# ADS1282.net
KiCad netlist of a schematic drawn in Altium Designer
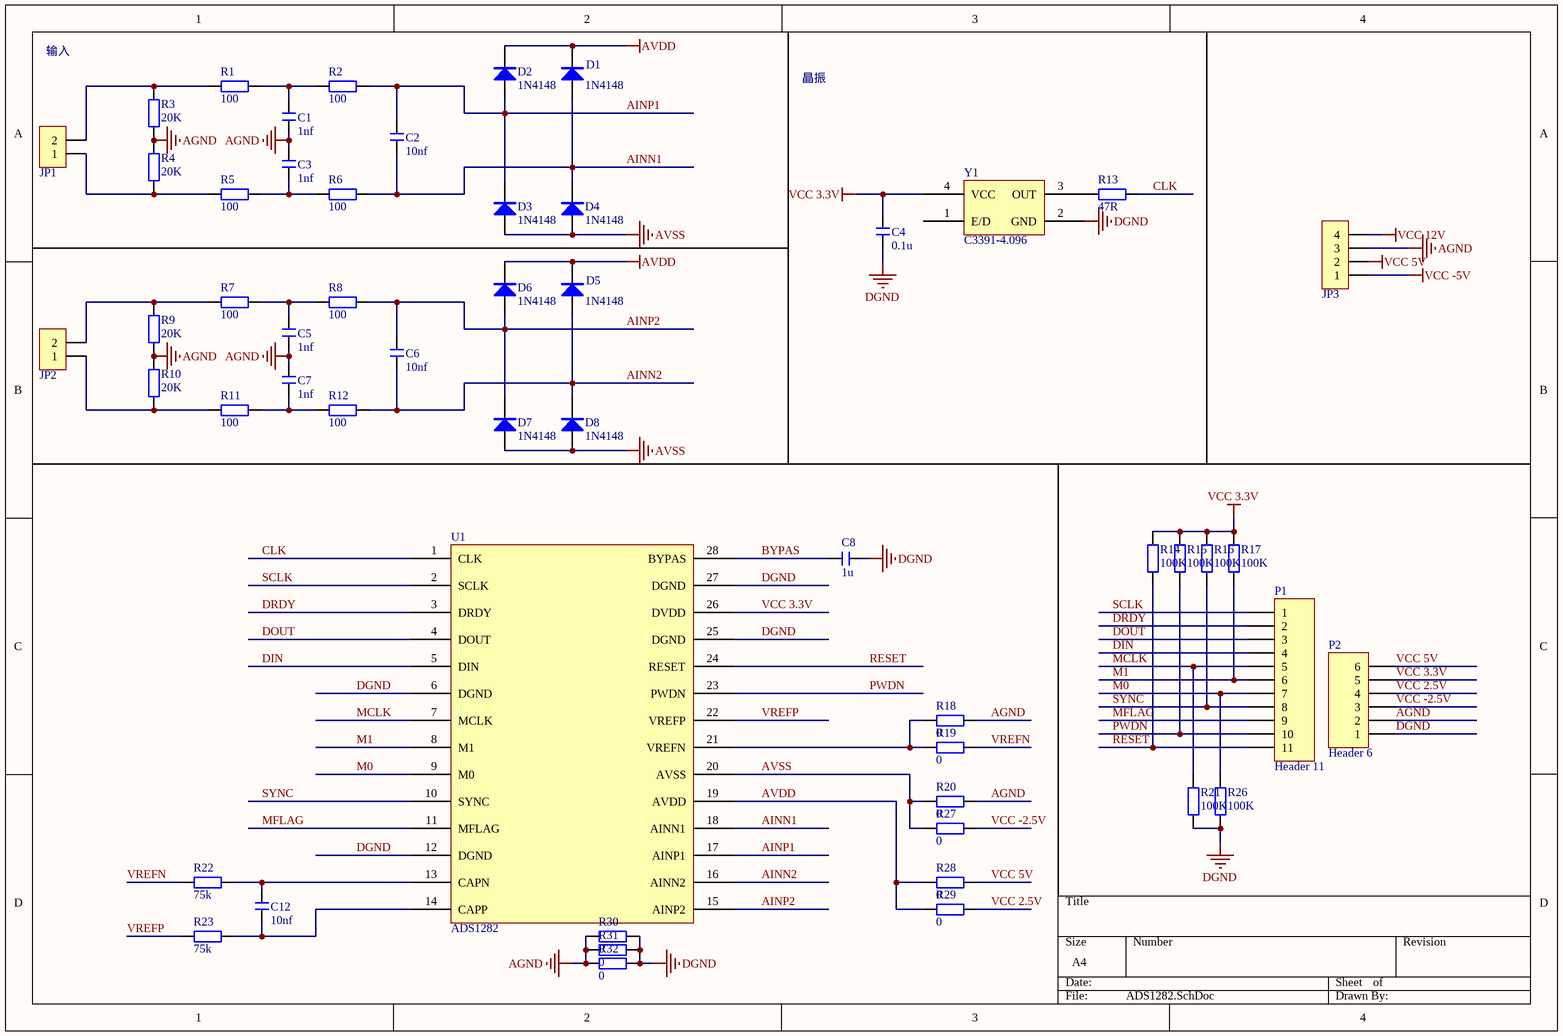
[diagram p0: ADS1282.SchDoc]

(export (version "E")
  (design (tool "Eeschema 10.0.6"))
  (components
    (comp (ref "C1")
      (value "1nf")
      (footprint "C 0805_L")
      (description "无极性贴片电容")
      (fields (field (name "版权归属") "源创客"))
      (libsource (lib "3.1   - 电阻-电容-电感") (part "C"))
    )
    (comp (ref "C2")
      (value "10nf")
      (footprint "C 0805_L")
      (description "无极性贴片电容")
      (fields (field (name "版权归属") "源创客"))
      (libsource (lib "3.1   - 电阻-电容-电感") (part "C"))
    )
    (comp (ref "C3")
      (value "1nf")
      (footprint "C 0805_L")
      (description "无极性贴片电容")
      (fields (field (name "版权归属") "源创客"))
      (libsource (lib "3.1   - 电阻-电容-电感") (part "C"))
    )
    (comp (ref "C4")
      (value "0.1u")
      (footprint "C 0805_L")
      (description "无极性贴片电容")
      (fields (field (name "版权归属") "源创客"))
      (libsource (lib "3.1   - 电阻-电容-电感") (part "C"))
    )
    (comp (ref "C5")
      (value "1nf")
      (footprint "C 0805_L")
      (description "无极性贴片电容")
      (fields (field (name "版权归属") "源创客"))
      (libsource (lib "3.1   - 电阻-电容-电感") (part "C"))
    )
    (comp (ref "C6")
      (value "10nf")
      (footprint "C 0805_L")
      (description "无极性贴片电容")
      (fields (field (name "版权归属") "源创客"))
      (libsource (lib "3.1   - 电阻-电容-电感") (part "C"))
    )
    (comp (ref "C7")
      (value "1nf")
      (footprint "C 0805_L")
      (description "无极性贴片电容")
      (fields (field (name "版权归属") "源创客"))
      (libsource (lib "3.1   - 电阻-电容-电感") (part "C"))
    )
    (comp (ref "C8")
      (value "1u")
      (footprint "C 0805_L")
      (description "无极性贴片电容")
      (fields (field (name "版权归属") "源创客"))
      (libsource (lib "3.1   - 电阻-电容-电感") (part "C"))
    )
    (comp (ref "C12")
      (value "10nf")
      (footprint "C 0805_L")
      (description "无极性贴片电容")
      (fields (field (name "版权归属") "源创客"))
      (libsource (lib "3.1   - 电阻-电容-电感") (part "C"))
    )
    (comp (ref "D1")
      (value "1N4148")
      (footprint "SOD-523")
      (description "高速开关二极管")
      (fields (field (name "版权归属") "源创客"))
      (libsource (lib "8.1   - 二极管-整流桥") (part "1N4148"))
    )
    (comp (ref "D2")
      (value "1N4148")
      (footprint "SOD-523")
      (description "高速开关二极管")
      (fields (field (name "版权归属") "源创客"))
      (libsource (lib "8.1   - 二极管-整流桥") (part "1N4148"))
    )
    (comp (ref "D3")
      (value "1N4148")
      (footprint "SOD-523")
      (description "高速开关二极管")
      (fields (field (name "版权归属") "源创客"))
      (libsource (lib "8.1   - 二极管-整流桥") (part "1N4148"))
    )
    (comp (ref "D4")
      (value "1N4148")
      (footprint "SOD-523")
      (description "高速开关二极管")
      (fields (field (name "版权归属") "源创客"))
      (libsource (lib "8.1   - 二极管-整流桥") (part "1N4148"))
    )
    (comp (ref "D5")
      (value "1N4148")
      (footprint "SOD-523")
      (description "高速开关二极管")
      (fields (field (name "版权归属") "源创客"))
      (libsource (lib "8.1   - 二极管-整流桥") (part "1N4148"))
    )
    (comp (ref "D6")
      (value "1N4148")
      (footprint "SOD-523")
      (description "高速开关二极管")
      (fields (field (name "版权归属") "源创客"))
      (libsource (lib "8.1   - 二极管-整流桥") (part "1N4148"))
    )
    (comp (ref "D7")
      (value "1N4148")
      (footprint "SOD-523")
      (description "高速开关二极管")
      (fields (field (name "版权归属") "源创客"))
      (libsource (lib "8.1   - 二极管-整流桥") (part "1N4148"))
    )
    (comp (ref "D8")
      (value "1N4148")
      (footprint "SOD-523")
      (description "高速开关二极管")
      (fields (field (name "版权归属") "源创客"))
      (libsource (lib "8.1   - 二极管-整流桥") (part "1N4148"))
    )
    (comp (ref "JP1")
      (value "HDR-1X2")
      (footprint "KF2EDGK5.08-LI-2P")
      (description "2P接插件")
      (fields (field (name "版权归属") "源创客"))
      (libsource (lib "4.10 - 接插件-脚距5.08") (part "Header 2"))
    )
    (comp (ref "JP2")
      (value "HDR-1X2")
      (footprint "KF2EDGK5.08-LI-2P")
      (description "2P接插件")
      (fields (field (name "版权归属") "源创客"))
      (libsource (lib "4.10 - 接插件-脚距5.08") (part "Header 2"))
    )
    (comp (ref "JP3")
      (value "HDR-1X4")
      (footprint "KF2EDGK5.08-LI-4P")
      (description "4P接插件")
      (fields (field (name "版权归属") "源创客"))
      (libsource (lib "4.10 - 接插件-脚距5.08") (part "Header 4"))
    )
    (comp (ref "P1")
      (value "Header 11")
      (footprint "HDR1X11")
      (description "Header, 11-Pin")
      (fields (field (name "PUBLISHER") "Altium Limited"))
      (libsource (lib "Miscellaneous Connectors") (part "Header 11"))
    )
    (comp (ref "P2")
      (value "Header 6")
      (footprint "HDR1X6")
      (description "Header, 6-Pin")
      (fields (field (name "PUBLISHER") "Altium Limited"))
      (libsource (lib "Miscellaneous Connectors") (part "Header 6"))
    )
    (comp (ref "R1")
      (value "100")
      (footprint "R 0805_L")
      (description "贴片电阻")
      (fields (field (name "版权归属") "源创客"))
      (libsource (lib "3.1   - 电阻-电容-电感") (part "R"))
    )
    (comp (ref "R2")
      (value "100")
      (footprint "R 0805_L")
      (description "贴片电阻")
      (fields (field (name "版权归属") "源创客"))
      (libsource (lib "3.1   - 电阻-电容-电感") (part "R"))
    )
    (comp (ref "R3")
      (value "20K")
      (footprint "R 0805_L")
      (description "贴片电阻")
      (fields (field (name "版权归属") "源创客"))
      (libsource (lib "3.1   - 电阻-电容-电感") (part "R"))
    )
    (comp (ref "R4")
      (value "20K")
      (footprint "R 0805_L")
      (description "贴片电阻")
      (fields (field (name "版权归属") "源创客"))
      (libsource (lib "3.1   - 电阻-电容-电感") (part "R"))
    )
    (comp (ref "R5")
      (value "100")
      (footprint "R 0805_L")
      (description "贴片电阻")
      (fields (field (name "版权归属") "源创客"))
      (libsource (lib "3.1   - 电阻-电容-电感") (part "R"))
    )
    (comp (ref "R6")
      (value "100")
      (footprint "R 0805_L")
      (description "贴片电阻")
      (fields (field (name "版权归属") "源创客"))
      (libsource (lib "3.1   - 电阻-电容-电感") (part "R"))
    )
    (comp (ref "R7")
      (value "100")
      (footprint "R 0805_L")
      (description "贴片电阻")
      (fields (field (name "版权归属") "源创客"))
      (libsource (lib "3.1   - 电阻-电容-电感") (part "R"))
    )
    (comp (ref "R8")
      (value "100")
      (footprint "R 0805_L")
      (description "贴片电阻")
      (fields (field (name "版权归属") "源创客"))
      (libsource (lib "3.1   - 电阻-电容-电感") (part "R"))
    )
    (comp (ref "R9")
      (value "20K")
      (footprint "R 0805_L")
      (description "贴片电阻")
      (fields (field (name "版权归属") "源创客"))
      (libsource (lib "3.1   - 电阻-电容-电感") (part "R"))
    )
    (comp (ref "R10")
      (value "20K")
      (footprint "R 0805_L")
      (description "贴片电阻")
      (fields (field (name "版权归属") "源创客"))
      (libsource (lib "3.1   - 电阻-电容-电感") (part "R"))
    )
    (comp (ref "R11")
      (value "100")
      (footprint "R 0805_L")
      (description "贴片电阻")
      (fields (field (name "版权归属") "源创客"))
      (libsource (lib "3.1   - 电阻-电容-电感") (part "R"))
    )
    (comp (ref "R12")
      (value "100")
      (footprint "R 0805_L")
      (description "贴片电阻")
      (fields (field (name "版权归属") "源创客"))
      (libsource (lib "3.1   - 电阻-电容-电感") (part "R"))
    )
    (comp (ref "R13")
      (value "47R")
      (footprint "R 0805_L")
      (description "贴片电阻")
      (fields (field (name "版权归属") "源创客"))
      (libsource (lib "3.1   - 电阻-电容-电感") (part "R"))
    )
    (comp (ref "R14")
      (value "100K")
      (footprint "R 0805_L")
      (description "贴片电阻")
      (fields (field (name "版权归属") "源创客"))
      (libsource (lib "3.1   - 电阻-电容-电感") (part "R"))
    )
    (comp (ref "R15")
      (value "100K")
      (footprint "R 0805_L")
      (description "贴片电阻")
      (fields (field (name "版权归属") "源创客"))
      (libsource (lib "3.1   - 电阻-电容-电感") (part "R"))
    )
    (comp (ref "R16")
      (value "100K")
      (footprint "R 0805_L")
      (description "贴片电阻")
      (fields (field (name "版权归属") "源创客"))
      (libsource (lib "3.1   - 电阻-电容-电感") (part "R"))
    )
    (comp (ref "R17")
      (value "100K")
      (footprint "R 0805_L")
      (description "贴片电阻")
      (fields (field (name "版权归属") "源创客"))
      (libsource (lib "3.1   - 电阻-电容-电感") (part "R"))
    )
    (comp (ref "R18")
      (value "0")
      (footprint "R 0603_L")
      (description "贴片电阻")
      (fields (field (name "版权归属") "源创客"))
      (libsource (lib "3.1   - 电阻-电容-电感") (part "R"))
    )
    (comp (ref "R19")
      (value "0")
      (footprint "R 0603_L")
      (description "贴片电阻")
      (fields (field (name "版权归属") "源创客"))
      (libsource (lib "3.1   - 电阻-电容-电感") (part "R"))
    )
    (comp (ref "R20")
      (value "0")
      (footprint "R 0603_L")
      (description "贴片电阻")
      (fields (field (name "版权归属") "源创客"))
      (libsource (lib "3.1   - 电阻-电容-电感") (part "R"))
    )
    (comp (ref "R21")
      (value "100K")
      (footprint "R 0805_L")
      (description "贴片电阻")
      (fields (field (name "版权归属") "源创客"))
      (libsource (lib "3.1   - 电阻-电容-电感") (part "R"))
    )
    (comp (ref "R22")
      (value "75k")
      (footprint "R 0805_L")
      (description "贴片电阻")
      (fields (field (name "版权归属") "源创客"))
      (libsource (lib "3.1   - 电阻-电容-电感") (part "R"))
    )
    (comp (ref "R23")
      (value "75k")
      (footprint "R 0805_L")
      (description "贴片电阻")
      (fields (field (name "版权归属") "源创客"))
      (libsource (lib "3.1   - 电阻-电容-电感") (part "R"))
    )
    (comp (ref "R26")
      (value "100K")
      (footprint "R 0805_L")
      (description "贴片电阻")
      (fields (field (name "版权归属") "源创客"))
      (libsource (lib "3.1   - 电阻-电容-电感") (part "R"))
    )
    (comp (ref "R27")
      (value "0")
      (footprint "R 0603_L")
      (description "贴片电阻")
      (fields (field (name "版权归属") "源创客"))
      (libsource (lib "3.1   - 电阻-电容-电感") (part "R"))
    )
    (comp (ref "R28")
      (value "0")
      (footprint "R 0603_L")
      (description "贴片电阻")
      (fields (field (name "版权归属") "源创客"))
      (libsource (lib "3.1   - 电阻-电容-电感") (part "R"))
    )
    (comp (ref "R29")
      (value "0")
      (footprint "R 0603_L")
      (description "贴片电阻")
      (fields (field (name "版权归属") "源创客"))
      (libsource (lib "3.1   - 电阻-电容-电感") (part "R"))
    )
    (comp (ref "R30")
      (value "0")
      (footprint "R 0805_L")
      (description "贴片电阻")
      (fields (field (name "版权归属") "源创客"))
      (libsource (lib "3.1   - 电阻-电容-电感") (part "R"))
    )
    (comp (ref "R31")
      (value "0")
      (footprint "R 0805_L")
      (description "贴片电阻")
      (fields (field (name "版权归属") "源创客"))
      (libsource (lib "3.1   - 电阻-电容-电感") (part "R"))
    )
    (comp (ref "R32")
      (value "0")
      (footprint "R 0805_L")
      (description "贴片电阻")
      (fields (field (name "版权归属") "源创客"))
      (libsource (lib "3.1   - 电阻-电容-电感") (part "R"))
    )
    (comp (ref "U1") (value "ADS1282") (footprint "SSOP28_N") (libsource (lib "ADS1282") (part "ADS1282")))
    (comp (ref "Y1")
      (value "C3391-4.096")
      (footprint "OSC 3225-4P")
      (libsource (lib "4.096M有源晶振") (part "4.096M"))
    )
  )
  (nets
    (net (code "1") (name "/AINN1") (class "Default")
      (node (ref "C2") (pin "1") (pinfunction "1_1") (pintype "passive"))
      (node (ref "D1") (pin "1") (pinfunction "A_1") (pintype "passive"))
      (node (ref "D4") (pin "2") (pinfunction "K_2") (pintype "passive"))
      (node (ref "R6") (pin "2") (pinfunction "2_2") (pintype "passive"))
      (node (ref "U1") (pin "18") (pinfunction "AINN1_18") (pintype "passive"))
    )
    (net (code "2") (name "/AINN2") (class "Default")
      (node (ref "C6") (pin "1") (pinfunction "1_1") (pintype "passive"))
      (node (ref "D5") (pin "1") (pinfunction "A_1") (pintype "passive"))
      (node (ref "D8") (pin "2") (pinfunction "K_2") (pintype "passive"))
      (node (ref "R12") (pin "2") (pinfunction "2_2") (pintype "passive"))
      (node (ref "U1") (pin "16") (pinfunction "AINN2_16") (pintype "passive"))
    )
    (net (code "3") (name "/AINP1") (class "Default")
      (node (ref "C2") (pin "2") (pinfunction "2_2") (pintype "passive"))
      (node (ref "D2") (pin "1") (pinfunction "A_1") (pintype "passive"))
      (node (ref "D3") (pin "2") (pinfunction "K_2") (pintype "passive"))
      (node (ref "R2") (pin "2") (pinfunction "2_2") (pintype "passive"))
      (node (ref "U1") (pin "17") (pinfunction "AINP1_17") (pintype "passive"))
    )
    (net (code "4") (name "/AINP2") (class "Default")
      (node (ref "C6") (pin "2") (pinfunction "2_2") (pintype "passive"))
      (node (ref "D6") (pin "1") (pinfunction "A_1") (pintype "passive"))
      (node (ref "D7") (pin "2") (pinfunction "K_2") (pintype "passive"))
      (node (ref "R8") (pin "2") (pinfunction "2_2") (pintype "passive"))
      (node (ref "U1") (pin "15") (pinfunction "AINP2_15") (pintype "passive"))
    )
    (net (code "5") (name "/BYPAS") (class "Default")
      (node (ref "C8") (pin "1") (pinfunction "1_1") (pintype "passive"))
      (node (ref "U1") (pin "28") (pinfunction "BYPAS_28") (pintype "passive"))
    )
    (net (code "6") (name "/CLK") (class "Default")
      (node (ref "R13") (pin "2") (pinfunction "2_2") (pintype "passive"))
      (node (ref "U1") (pin "1") (pinfunction "CLK_1") (pintype "passive"))
    )
    (net (code "7") (name "/DIN") (class "Default")
      (node (ref "P1") (pin "4") (pinfunction "4_4") (pintype "passive"))
      (node (ref "U1") (pin "5") (pinfunction "DIN_5") (pintype "passive"))
    )
    (net (code "8") (name "/DOUT") (class "Default")
      (node (ref "P1") (pin "3") (pinfunction "3_3") (pintype "passive"))
      (node (ref "U1") (pin "4") (pinfunction "DOUT_4") (pintype "passive"))
    )
    (net (code "9") (name "/DRDY") (class "Default")
      (node (ref "P1") (pin "2") (pinfunction "2_2") (pintype "passive"))
      (node (ref "U1") (pin "3") (pinfunction "DRDY_3") (pintype "passive"))
    )
    (net (code "10") (name "/M0") (class "Default")
      (node (ref "P1") (pin "7") (pinfunction "7_7") (pintype "passive"))
      (node (ref "R26") (pin "2") (pinfunction "2_2") (pintype "passive"))
      (node (ref "U1") (pin "9") (pinfunction "M0_9") (pintype "passive"))
    )
    (net (code "11") (name "/M1") (class "Default")
      (node (ref "P1") (pin "6") (pinfunction "6_6") (pintype "passive"))
      (node (ref "R17") (pin "1") (pinfunction "1_1") (pintype "passive"))
      (node (ref "U1") (pin "8") (pinfunction "M1_8") (pintype "passive"))
    )
    (net (code "12") (name "/MCLK") (class "Default")
      (node (ref "P1") (pin "5") (pinfunction "5_5") (pintype "passive"))
      (node (ref "R21") (pin "2") (pinfunction "2_2") (pintype "passive"))
      (node (ref "U1") (pin "7") (pinfunction "MCLK_7") (pintype "passive"))
    )
    (net (code "13") (name "/MFLAG") (class "Default")
      (node (ref "P1") (pin "9") (pinfunction "9_9") (pintype "passive"))
      (node (ref "U1") (pin "11") (pinfunction "MFLAG_11") (pintype "passive"))
    )
    (net (code "14") (name "/PWDN") (class "Default")
      (node (ref "P1") (pin "10") (pinfunction "10_10") (pintype "passive"))
      (node (ref "R15") (pin "1") (pinfunction "1_1") (pintype "passive"))
      (node (ref "U1") (pin "23") (pinfunction "PWDN_23") (pintype "passive"))
    )
    (net (code "15") (name "/RESET") (class "Default")
      (node (ref "P1") (pin "11") (pinfunction "11_11") (pintype "passive"))
      (node (ref "R14") (pin "1") (pinfunction "1_1") (pintype "passive"))
      (node (ref "U1") (pin "24") (pinfunction "RESET_24") (pintype "passive"))
    )
    (net (code "16") (name "/SCLK") (class "Default")
      (node (ref "P1") (pin "1") (pinfunction "1_1") (pintype "passive"))
      (node (ref "U1") (pin "2") (pinfunction "SCLK_2") (pintype "passive"))
    )
    (net (code "17") (name "/SYNC") (class "Default")
      (node (ref "P1") (pin "8") (pinfunction "8_8") (pintype "passive"))
      (node (ref "R16") (pin "1") (pinfunction "1_1") (pintype "passive"))
      (node (ref "U1") (pin "10") (pinfunction "SYNC_10") (pintype "passive"))
    )
    (net (code "18") (name "/VCC -2.5V") (class "Default")
      (node (ref "P2") (pin "3") (pinfunction "3_3") (pintype "passive"))
      (node (ref "R27") (pin "2") (pinfunction "2_2") (pintype "passive"))
    )
    (net (code "19") (name "/VCC 2.5V") (class "Default")
      (node (ref "P2") (pin "4") (pinfunction "4_4") (pintype "passive"))
      (node (ref "R29") (pin "2") (pinfunction "2_2") (pintype "passive"))
    )
    (net (code "20") (name "/VREFN") (class "Default")
      (node (ref "R19") (pin "2") (pinfunction "2_2") (pintype "passive"))
      (node (ref "R22") (pin "1") (pinfunction "1_1") (pintype "passive"))
    )
    (net (code "21") (name "/VREFP") (class "Default")
      (node (ref "R23") (pin "1") (pinfunction "1_1") (pintype "passive"))
      (node (ref "U1") (pin "22") (pinfunction "VREFP_22") (pintype "passive"))
    )
    (net (code "22") (name "AGND") (class "Default")
      (node (ref "C1") (pin "1") (pinfunction "1_1") (pintype "passive"))
      (node (ref "C3") (pin "2") (pinfunction "2_2") (pintype "passive"))
      (node (ref "C5") (pin "1") (pinfunction "1_1") (pintype "passive"))
      (node (ref "C7") (pin "2") (pinfunction "2_2") (pintype "passive"))
      (node (ref "JP3") (pin "3") (pinfunction "3_3") (pintype "passive"))
      (node (ref "P2") (pin "2") (pinfunction "2_2") (pintype "passive"))
      (node (ref "R10") (pin "2") (pinfunction "2_2") (pintype "passive"))
      (node (ref "R18") (pin "2") (pinfunction "2_2") (pintype "passive"))
      (node (ref "R20") (pin "2") (pinfunction "2_2") (pintype "passive"))
      (node (ref "R3") (pin "1") (pinfunction "1_1") (pintype "passive"))
      (node (ref "R30") (pin "1") (pinfunction "1_1") (pintype "passive"))
      (node (ref "R31") (pin "1") (pinfunction "1_1") (pintype "passive"))
      (node (ref "R32") (pin "1") (pinfunction "1_1") (pintype "passive"))
      (node (ref "R4") (pin "2") (pinfunction "2_2") (pintype "passive"))
      (node (ref "R9") (pin "1") (pinfunction "1_1") (pintype "passive"))
    )
    (net (code "23") (name "AVDD") (class "Default")
      (node (ref "D1") (pin "2") (pinfunction "K_2") (pintype "passive"))
      (node (ref "D2") (pin "2") (pinfunction "K_2") (pintype "passive"))
      (node (ref "D5") (pin "2") (pinfunction "K_2") (pintype "passive"))
      (node (ref "D6") (pin "2") (pinfunction "K_2") (pintype "passive"))
      (node (ref "R28") (pin "1") (pinfunction "1_1") (pintype "passive"))
      (node (ref "R29") (pin "1") (pinfunction "1_1") (pintype "passive"))
      (node (ref "U1") (pin "19") (pinfunction "AVDD_19") (pintype "passive"))
    )
    (net (code "24") (name "AVSS") (class "Default")
      (node (ref "D3") (pin "1") (pinfunction "A_1") (pintype "passive"))
      (node (ref "D4") (pin "1") (pinfunction "A_1") (pintype "passive"))
      (node (ref "D7") (pin "1") (pinfunction "A_1") (pintype "passive"))
      (node (ref "D8") (pin "1") (pinfunction "A_1") (pintype "passive"))
      (node (ref "R20") (pin "1") (pinfunction "1_1") (pintype "passive"))
      (node (ref "R27") (pin "1") (pinfunction "1_1") (pintype "passive"))
      (node (ref "U1") (pin "20") (pinfunction "AVSS_20") (pintype "passive"))
    )
    (net (code "25") (name "DGND") (class "Default")
      (node (ref "C4") (pin "1") (pinfunction "1_1") (pintype "passive"))
      (node (ref "C8") (pin "2") (pinfunction "2_2") (pintype "passive"))
      (node (ref "P2") (pin "1") (pinfunction "1_1") (pintype "passive"))
      (node (ref "R21") (pin "1") (pinfunction "1_1") (pintype "passive"))
      (node (ref "R26") (pin "1") (pinfunction "1_1") (pintype "passive"))
      (node (ref "R30") (pin "2") (pinfunction "2_2") (pintype "passive"))
      (node (ref "R31") (pin "2") (pinfunction "2_2") (pintype "passive"))
      (node (ref "R32") (pin "2") (pinfunction "2_2") (pintype "passive"))
      (node (ref "U1") (pin "12") (pinfunction "DGND_12") (pintype "passive"))
      (node (ref "U1") (pin "25") (pinfunction "DGND_25") (pintype "passive"))
      (node (ref "U1") (pin "27") (pinfunction "DGND_27") (pintype "passive"))
      (node (ref "U1") (pin "6") (pinfunction "DGND_6") (pintype "passive"))
      (node (ref "Y1") (pin "2") (pinfunction "GND_2") (pintype "passive"))
    )
    (net (code "26") (name "Net-(C1-Pad2)") (class "Default")
      (node (ref "C1") (pin "2") (pinfunction "2_2") (pintype "passive"))
      (node (ref "R1") (pin "2") (pinfunction "2_2") (pintype "passive"))
      (node (ref "R2") (pin "1") (pinfunction "1_1") (pintype "passive"))
    )
    (net (code "27") (name "Net-(C3-Pad1)") (class "Default")
      (node (ref "C3") (pin "1") (pinfunction "1_1") (pintype "passive"))
      (node (ref "R5") (pin "2") (pinfunction "2_2") (pintype "passive"))
      (node (ref "R6") (pin "1") (pinfunction "1_1") (pintype "passive"))
    )
    (net (code "28") (name "Net-(C5-Pad2)") (class "Default")
      (node (ref "C5") (pin "2") (pinfunction "2_2") (pintype "passive"))
      (node (ref "R7") (pin "2") (pinfunction "2_2") (pintype "passive"))
      (node (ref "R8") (pin "1") (pinfunction "1_1") (pintype "passive"))
    )
    (net (code "29") (name "Net-(C7-Pad1)") (class "Default")
      (node (ref "C7") (pin "1") (pinfunction "1_1") (pintype "passive"))
      (node (ref "R11") (pin "2") (pinfunction "2_2") (pintype "passive"))
      (node (ref "R12") (pin "1") (pinfunction "1_1") (pintype "passive"))
    )
    (net (code "30") (name "Net-(JP1-Pad1)") (class "Default")
      (node (ref "JP1") (pin "1") (pinfunction "1_1") (pintype "passive"))
      (node (ref "R4") (pin "1") (pinfunction "1_1") (pintype "passive"))
      (node (ref "R5") (pin "1") (pinfunction "1_1") (pintype "passive"))
    )
    (net (code "31") (name "Net-(JP1-Pad2)") (class "Default")
      (node (ref "JP1") (pin "2") (pinfunction "2_2") (pintype "passive"))
      (node (ref "R1") (pin "1") (pinfunction "1_1") (pintype "passive"))
      (node (ref "R3") (pin "2") (pinfunction "2_2") (pintype "passive"))
    )
    (net (code "32") (name "Net-(JP2-Pad1)") (class "Default")
      (node (ref "JP2") (pin "1") (pinfunction "1_1") (pintype "passive"))
      (node (ref "R10") (pin "1") (pinfunction "1_1") (pintype "passive"))
      (node (ref "R11") (pin "1") (pinfunction "1_1") (pintype "passive"))
    )
    (net (code "33") (name "Net-(JP2-Pad2)") (class "Default")
      (node (ref "JP2") (pin "2") (pinfunction "2_2") (pintype "passive"))
      (node (ref "R7") (pin "1") (pinfunction "1_1") (pintype "passive"))
      (node (ref "R9") (pin "2") (pinfunction "2_2") (pintype "passive"))
    )
    (net (code "34") (name "Net-(U1-CAPN)") (class "Default")
      (node (ref "C12") (pin "2") (pinfunction "2_2") (pintype "passive"))
      (node (ref "R22") (pin "2") (pinfunction "2_2") (pintype "passive"))
      (node (ref "U1") (pin "13") (pinfunction "CAPN_13") (pintype "passive"))
    )
    (net (code "35") (name "Net-(U1-CAPP)") (class "Default")
      (node (ref "C12") (pin "1") (pinfunction "1_1") (pintype "passive"))
      (node (ref "R23") (pin "2") (pinfunction "2_2") (pintype "passive"))
      (node (ref "U1") (pin "14") (pinfunction "CAPP_14") (pintype "passive"))
    )
    (net (code "36") (name "Net-(U1-VREFN)") (class "Default")
      (node (ref "R18") (pin "1") (pinfunction "1_1") (pintype "passive"))
      (node (ref "R19") (pin "1") (pinfunction "1_1") (pintype "passive"))
      (node (ref "U1") (pin "21") (pinfunction "VREFN_21") (pintype "passive"))
    )
    (net (code "37") (name "Net-(Y1-OUT)") (class "Default")
      (node (ref "R13") (pin "1") (pinfunction "1_1") (pintype "passive"))
      (node (ref "Y1") (pin "3") (pinfunction "OUT_3") (pintype "passive"))
    )
    (net (code "38") (name "VCC -5V") (class "Default")
      (node (ref "JP3") (pin "1") (pinfunction "1_1") (pintype "passive"))
    )
    (net (code "39") (name "VCC 3.3V") (class "Default")
      (node (ref "C4") (pin "2") (pinfunction "2_2") (pintype "passive"))
      (node (ref "P2") (pin "5") (pinfunction "5_5") (pintype "passive"))
      (node (ref "R14") (pin "2") (pinfunction "2_2") (pintype "passive"))
      (node (ref "R15") (pin "2") (pinfunction "2_2") (pintype "passive"))
      (node (ref "R16") (pin "2") (pinfunction "2_2") (pintype "passive"))
      (node (ref "R17") (pin "2") (pinfunction "2_2") (pintype "passive"))
      (node (ref "U1") (pin "26") (pinfunction "DVDD_26") (pintype "passive"))
      (node (ref "Y1") (pin "4") (pinfunction "VCC_4") (pintype "passive"))
    )
    (net (code "40") (name "VCC 5V") (class "Default")
      (node (ref "JP3") (pin "2") (pinfunction "2_2") (pintype "passive"))
      (node (ref "P2") (pin "6") (pinfunction "6_6") (pintype "passive"))
      (node (ref "R28") (pin "2") (pinfunction "2_2") (pintype "passive"))
    )
    (net (code "41") (name "VCC 12V") (class "Default")
      (node (ref "JP3") (pin "4") (pinfunction "4_4") (pintype "passive"))
    )
    (net (code "42") (name "unconnected-(Y1-E{slash}D-Pad1)") (class "Default")
      (node (ref "Y1") (pin "1") (pinfunction "E/D_1") (pintype "passive"))
    )
  )
)
